# leo_power_sch.net
KiCad netlist of a schematic drawn in Altium Designer
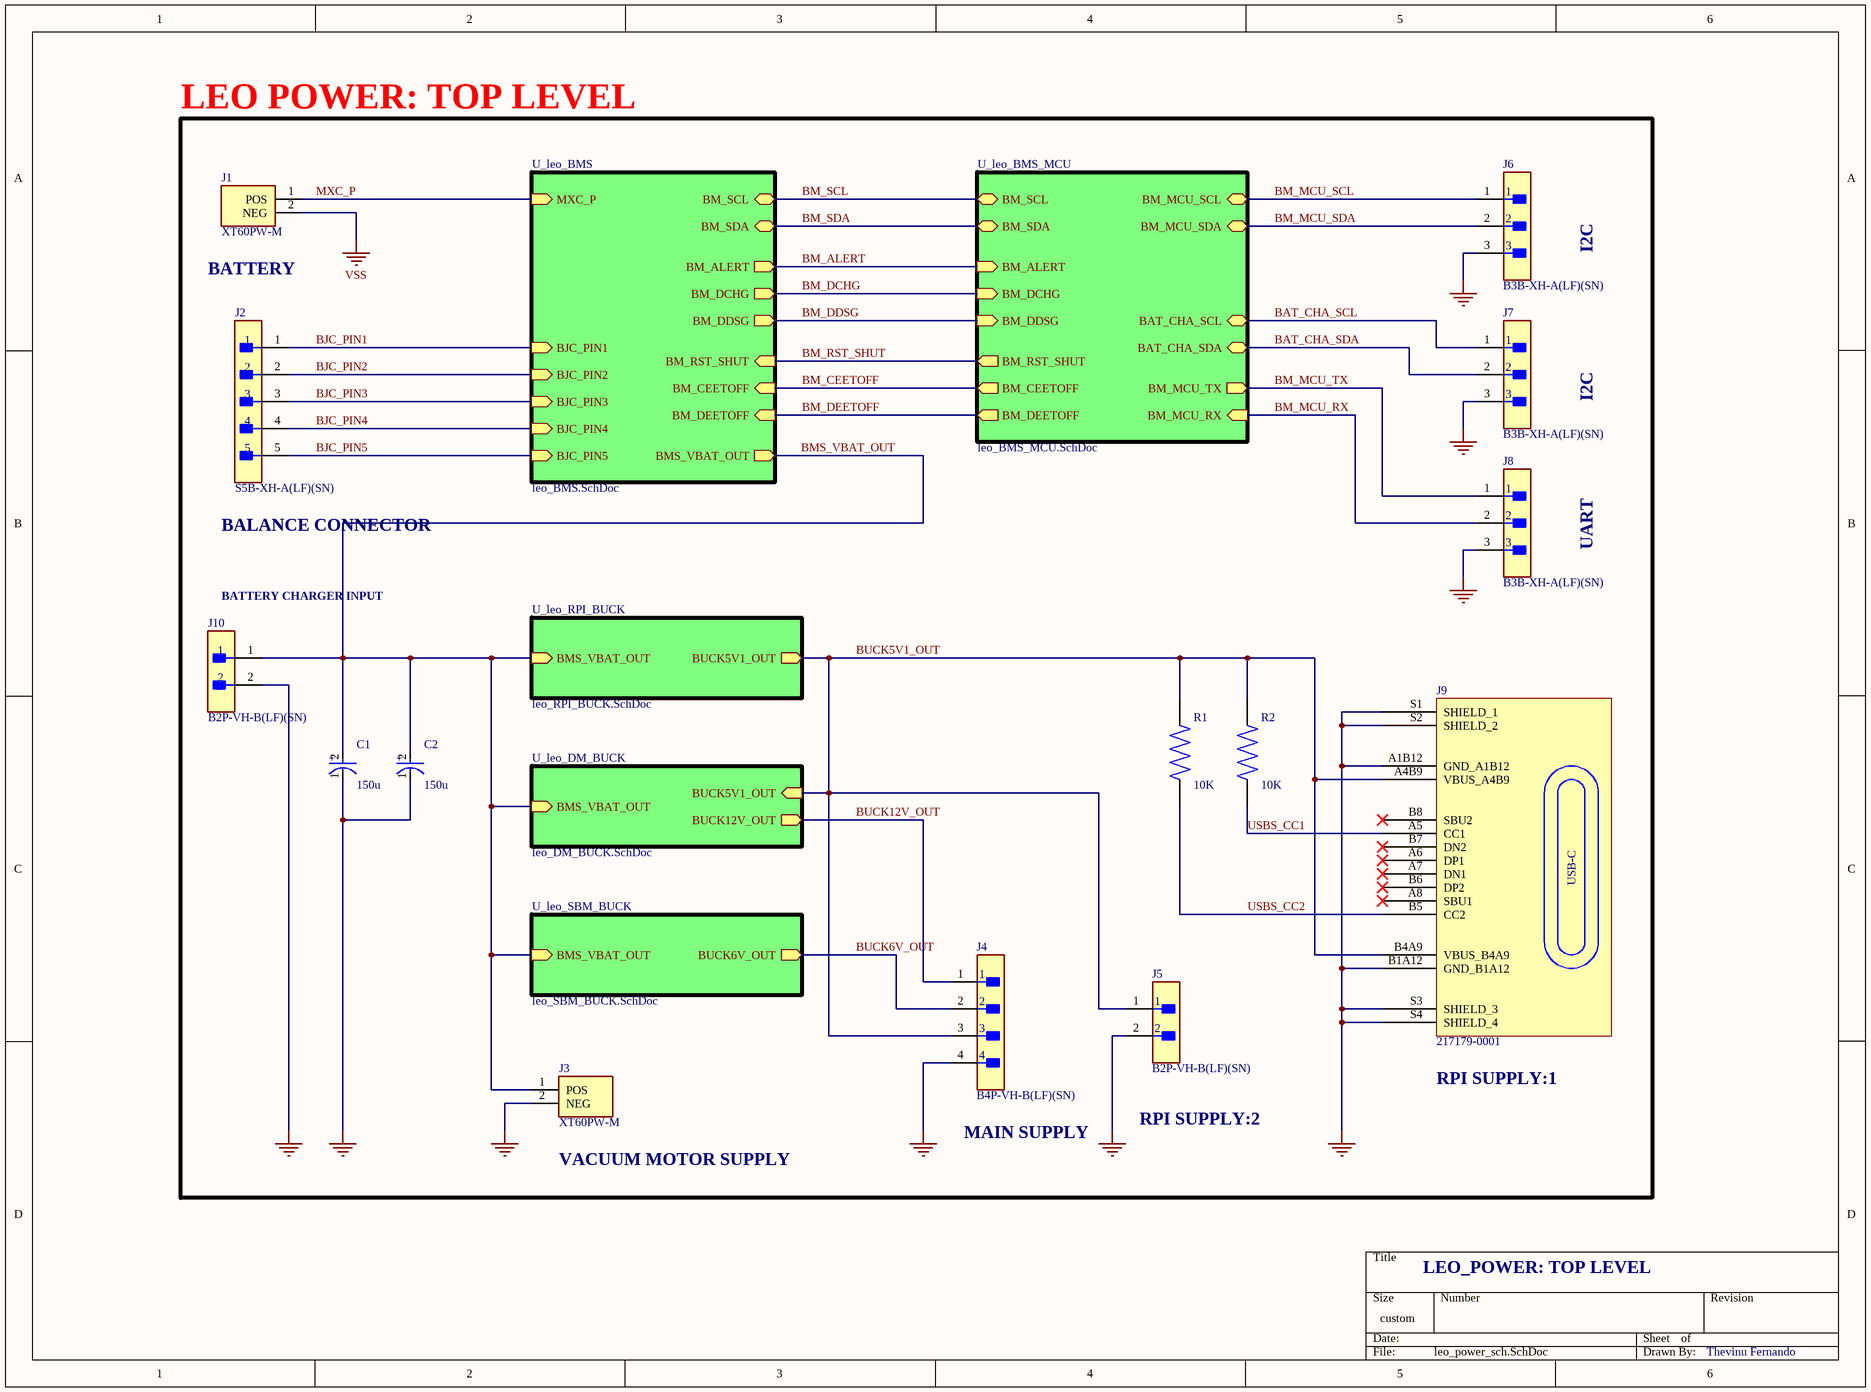
[diagram p0: leo_power_sch.SchDoc]

(export (version "E")
  (design (tool "Eeschema 10.0.6"))
  (components
    (comp (ref "C1")
      (value "150u")
      (footprint "FP-FTD8-MFG")
      (description "CAP ALUM 150UF 20% 35V SMD")
      (fields (field (name "TOLERANCE") "20%") (field (name "VOLTAGE") "35V"))
      (libsource (lib "leo_power_schlib") (part "EEEFTV151XAP"))
    )
    (comp (ref "C2")
      (value "150u")
      (footprint "FP-FTD8-MFG")
      (description "CAP ALUM 150UF 20% 35V SMD")
      (fields (field (name "TOLERANCE") "20%") (field (name "VOLTAGE") "35V"))
      (libsource (lib "leo_power_schlib") (part "EEEFTV151XAP"))
    )
    (comp (ref "J1")
      (value "XT60PW-M")
      (footprint "AMASS_XT60PW-M")
      (description "Socket, DC supply, male, PIN: 2")
      (fields (field (name "MF") "AMASS"))
      (libsource (lib "leo_power_schlib") (part "XT60PW-M"))
    )
    (comp (ref "J2")
      (value "S5B-XH-A(LF)(SN)")
      (footprint "FP-S5B-XH-A_LF_SN-MFG")
      (description "CONN HEADER R/A 5POS 2.5MM")
      (libsource (lib "leo_power_schlib") (part "S5B-XH-A(LF)(SN)"))
    )
    (comp (ref "J3")
      (value "XT60PW-M")
      (footprint "AMASS_XT60PW-M")
      (description "Socket, DC supply, male, PIN: 2")
      (fields (field (name "MF") "AMASS"))
      (libsource (lib "") (part "XT60PW-M_1"))
    )
    (comp (ref "J4")
      (value "B4P-VH-B(LF)(SN)")
      (footprint "FP-B4P-VH-B_LF_SN-MFG")
      (description "CONN HEADER VERT 4POS 3.96MM")
      (libsource (lib "leo_power_schlib") (part "B4P-VH-B(LF)(SN)"))
    )
    (comp (ref "J5")
      (value "B2P-VH-B(LF)(SN)")
      (footprint "FP-B2P-VH-B_LF_SN-MFG")
      (description "CONN HEADER VERT 2POS 3.96MM")
      (libsource (lib "") (part "B2P-VH-B(LF)(SN)_1"))
    )
    (comp (ref "J6")
      (value "B3B-XH-A(LF)(SN)")
      (footprint "FP-B3B-XH-A_LF_SN-MFG")
      (description "CONN HEADER VERT 3POS 2.5MM")
      (libsource (lib "leo_power_schlib") (part "B3B-XH-A(LF)(SN)"))
    )
    (comp (ref "J7")
      (value "B3B-XH-A(LF)(SN)")
      (footprint "FP-B3B-XH-A_LF_SN-MFG")
      (description "CONN HEADER VERT 3POS 2.5MM")
      (libsource (lib "leo_power_schlib") (part "B3B-XH-A(LF)(SN)"))
    )
    (comp (ref "J8")
      (value "B3B-XH-A(LF)(SN)")
      (footprint "FP-B3B-XH-A_LF_SN-MFG")
      (description "CONN HEADER VERT 3POS 2.5MM")
      (libsource (lib "leo_power_schlib") (part "B3B-XH-A(LF)(SN)"))
    )
    (comp (ref "J9")
      (value "217179-0001")
      (footprint "FP-2171790001-MFG USB-C 2.0")
      (description "USB 2.0 5A 1 16P -40℃~+85℃ SMD USB, DVI, HDMI Connector Assemblies RoHS")
      (fields (field (name "MANUFACTURER") "Molex") (field (name "LCSC PART NUMBER") "C3197684"))
      (libsource (lib "leo_power_schlib") (part "USB_Connector"))
    )
    (comp (ref "J10")
      (value "B2P-VH-B(LF)(SN)")
      (footprint "FP-B2P-VH-B_LF_SN-MFG")
      (description "CONN HEADER VERT 2POS 3.96MM")
      (libsource (lib "leo_power_schlib") (part "B2P-VH-B(LF)(SN)"))
    )
    (comp (ref "R1")
      (value "10K")
      (footprint "RES_0402")
      (description "Chip Resistor 0402 (1005 Metric) Automotive AEC-Q200 Thick Film")
      (fields (field (name "MF") "Panasonic") (field (name "MP") "ERJ-2RKF1002X"))
      (libsource (lib "leo_power_schlib") (part "RES_0402"))
    )
    (comp (ref "R2")
      (value "10K")
      (footprint "RES_0402")
      (description "Chip Resistor 0402 (1005 Metric) Automotive AEC-Q200 Thick Film")
      (fields (field (name "MF") "Panasonic") (field (name "MP") "ERJ-2RKF1002X"))
      (libsource (lib "leo_power_schlib") (part "RES_0402"))
    )
  )
  (nets
    (net (code "1") (name "/BAT_CHA_SCL") (class "Default")
      (node (ref "J7") (pin "1") (pinfunction "1_1") (pintype "passive"))
    )
    (net (code "2") (name "/BAT_CHA_SDA") (class "Default")
      (node (ref "J7") (pin "2") (pinfunction "2_2") (pintype "passive"))
    )
    (net (code "3") (name "/BJC_PIN1") (class "Default")
      (node (ref "J2") (pin "1") (pinfunction "1_1") (pintype "passive"))
    )
    (net (code "4") (name "/BJC_PIN2") (class "Default")
      (node (ref "J2") (pin "2") (pinfunction "2_2") (pintype "passive"))
    )
    (net (code "5") (name "/BJC_PIN3") (class "Default")
      (node (ref "J2") (pin "3") (pinfunction "3_3") (pintype "passive"))
    )
    (net (code "6") (name "/BJC_PIN4") (class "Default")
      (node (ref "J2") (pin "4") (pinfunction "4_4") (pintype "passive"))
    )
    (net (code "7") (name "/BJC_PIN5") (class "Default")
      (node (ref "J2") (pin "5") (pinfunction "5_5") (pintype "passive"))
    )
    (net (code "8") (name "/BMS_VBAT_OUT") (class "Default")
      (node (ref "C1") (pin "2") (pinfunction "A_2") (pintype "passive"))
      (node (ref "C2") (pin "2") (pinfunction "A_2") (pintype "passive"))
      (node (ref "J10") (pin "1") (pinfunction "1_1") (pintype "passive"))
      (node (ref "J3") (pin "1") (pinfunction "POS_1") (pintype "passive"))
    )
    (net (code "14") (name "/BM_MCU_RX") (class "Default")
      (node (ref "J8") (pin "2") (pinfunction "2_2") (pintype "passive"))
    )
    (net (code "15") (name "/BM_MCU_SCL") (class "Default")
      (node (ref "J6") (pin "1") (pinfunction "1_1") (pintype "passive"))
    )
    (net (code "16") (name "/BM_MCU_SDA") (class "Default")
      (node (ref "J6") (pin "2") (pinfunction "2_2") (pintype "passive"))
    )
    (net (code "17") (name "/BM_MCU_TX") (class "Default")
      (node (ref "J8") (pin "1") (pinfunction "1_1") (pintype "passive"))
    )
    (net (code "21") (name "/BUCK5V1_OUT") (class "Default")
      (node (ref "J4") (pin "3") (pinfunction "3_3") (pintype "passive"))
      (node (ref "J5") (pin "1") (pinfunction "1_1") (pintype "passive"))
      (node (ref "J9") (pin "A4B9") (pinfunction "VBUS_A4B9_A4B9") (pintype "passive"))
      (node (ref "J9") (pin "B4A9") (pinfunction "VBUS_B4A9_B4A9") (pintype "passive"))
      (node (ref "R1") (pin "2") (pinfunction "2_2") (pintype "passive"))
      (node (ref "R2") (pin "2") (pinfunction "2_2") (pintype "passive"))
    )
    (net (code "22") (name "/BUCK6V_OUT") (class "Default")
      (node (ref "J4") (pin "2") (pinfunction "2_2") (pintype "passive"))
    )
    (net (code "23") (name "/BUCK12V_OUT") (class "Default")
      (node (ref "J4") (pin "1") (pinfunction "1_1") (pintype "passive"))
    )
    (net (code "24") (name "/MXC_P") (class "Default")
      (node (ref "J1") (pin "1") (pinfunction "POS_1") (pintype "passive"))
    )
    (net (code "25") (name "/USBS_CC1") (class "Default")
      (node (ref "J9") (pin "A5") (pinfunction "CC1_A5") (pintype "passive"))
      (node (ref "R2") (pin "1") (pinfunction "1_1") (pintype "passive"))
    )
    (net (code "26") (name "/USBS_CC2") (class "Default")
      (node (ref "J9") (pin "B5") (pinfunction "CC2_B5") (pintype "passive"))
      (node (ref "R1") (pin "1") (pinfunction "1_1") (pintype "passive"))
    )
    (net (code "27") (name "GND") (class "Default")
      (node (ref "C1") (pin "1") (pinfunction "C_1") (pintype "passive"))
      (node (ref "C2") (pin "1") (pinfunction "C_1") (pintype "passive"))
      (node (ref "J10") (pin "2") (pinfunction "2_2") (pintype "passive"))
      (node (ref "J3") (pin "2") (pinfunction "NEG_2") (pintype "passive"))
      (node (ref "J4") (pin "4") (pinfunction "4_4") (pintype "passive"))
      (node (ref "J5") (pin "2") (pinfunction "2_2") (pintype "passive"))
      (node (ref "J6") (pin "3") (pinfunction "3_3") (pintype "passive"))
      (node (ref "J7") (pin "3") (pinfunction "3_3") (pintype "passive"))
      (node (ref "J8") (pin "3") (pinfunction "3_3") (pintype "passive"))
      (node (ref "J9") (pin "A1B12") (pinfunction "GND_A1B12_A1B12") (pintype "passive"))
      (node (ref "J9") (pin "B1A12") (pinfunction "GND_B1A12_B1A12") (pintype "passive"))
      (node (ref "J9") (pin "S1") (pinfunction "SHIELD_1_S1") (pintype "passive"))
      (node (ref "J9") (pin "S2") (pinfunction "SHIELD_2_S2") (pintype "passive"))
      (node (ref "J9") (pin "S3") (pinfunction "SHIELD_3_S3") (pintype "passive"))
      (node (ref "J9") (pin "S4") (pinfunction "SHIELD_4_S4") (pintype "passive"))
    )
    (net (code "28") (name "VSS") (class "Default")
      (node (ref "J1") (pin "2") (pinfunction "NEG_2") (pintype "passive"))
    )
    (net (code "29") (name "unconnected-(J9-DN1-PadA7)") (class "Default")
      (node (ref "J9") (pin "A7") (pinfunction "DN1_A7") (pintype "passive+no_connect"))
    )
    (net (code "30") (name "unconnected-(J9-DN2-PadB7)") (class "Default")
      (node (ref "J9") (pin "B7") (pinfunction "DN2_B7") (pintype "passive+no_connect"))
    )
    (net (code "31") (name "unconnected-(J9-DP1-PadA6)") (class "Default")
      (node (ref "J9") (pin "A6") (pinfunction "DP1_A6") (pintype "passive+no_connect"))
    )
    (net (code "32") (name "unconnected-(J9-DP2-PadB6)") (class "Default")
      (node (ref "J9") (pin "B6") (pinfunction "DP2_B6") (pintype "passive+no_connect"))
    )
    (net (code "33") (name "unconnected-(J9-SBU1-PadA8)") (class "Default")
      (node (ref "J9") (pin "A8") (pinfunction "SBU1_A8") (pintype "passive+no_connect"))
    )
    (net (code "34") (name "unconnected-(J9-SBU2-PadB8)") (class "Default")
      (node (ref "J9") (pin "B8") (pinfunction "SBU2_B8") (pintype "passive+no_connect"))
    )
  )
)
